# schematics.net
KiCad netlist of a schematic drawn in EAGLE
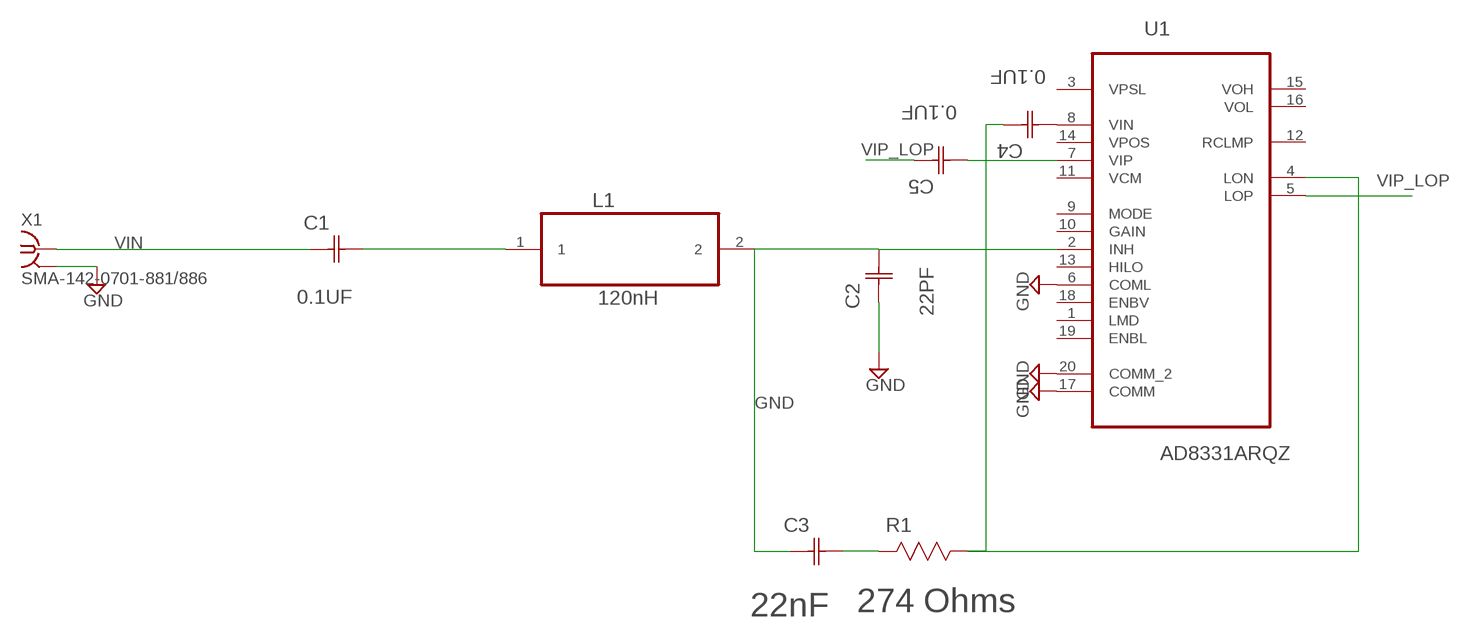
[diagram p0: schematic, sheet 1]

(export (version "E")
  (design (tool "Eeschema 10.0.6"))
  (components
    (comp (ref "C1")
      (value "0.1UF")
      (footprint "eagle-import:CAPC3216X94N")
      (fields (field (name "MPN") "12065C104JAT2A") (field (name "TOLERANCE") "± 5%"))
      (libsource (lib "eagle-import") (part "12065C104JAT2A"))
    )
    (comp (ref "C2")
      (value "22PF")
      (footprint "eagle-import:CAPC3216X94N")
      (fields (field (name "MPN") "12063A220JAT2A") (field (name "TOLERANCE") "±5%"))
      (libsource (lib "eagle-import") (part "12063A220JAT2A"))
    )
    (comp (ref "C3")
      (value "22nF")
      (footprint "eagle-import:CAPC2013X88N")
      (fields (field (name "MPN") "C0805F223K5RACAUTO") (field (name "TOLERANCE") "±10%"))
      (libsource (lib "eagle-import") (part "C0805F223K5RACAUTO"))
    )
    (comp (ref "C4")
      (value "0.1UF")
      (footprint "eagle-import:CAPC3216X94N")
      (fields (field (name "MPN") "12065C104JAT2A") (field (name "TOLERANCE") "± 5%"))
      (libsource (lib "eagle-import") (part "12065C104JAT2A"))
    )
    (comp (ref "C5")
      (value "0.1UF")
      (footprint "eagle-import:CAPC3216X94N")
      (fields (field (name "MPN") "12065C104JAT2A") (field (name "TOLERANCE") "± 5%"))
      (libsource (lib "eagle-import") (part "12065C104JAT2A"))
    )
    (comp (ref "L1")
      (value "120nH")
      (footprint "eagle-import:INDC2317X140N")
      (fields (field (name "MPN") "B82498F3121J") (field (name "TOLERANCE") "±5%"))
      (libsource (lib "eagle-import") (part "B82498F3121J"))
    )
    (comp (ref "R1")
      (value "274 Ohms")
      (footprint "eagle-import:RESC3216X71N")
      (fields (field (name "MPN") "CRCW1206274RFKEA") (field (name "TOLERANCE") "±1%"))
      (libsource (lib "eagle-import") (part "CRCW1206274RFKEA"))
    )
    (comp (ref "U1")
      (value "AD8331ARQZ")
      (footprint "eagle-import:SOP64P600X165-20N")
      (libsource (lib "eagle-import") (part "AD8331ARQZ"))
    )
    (comp (ref "X1")
      (value "SMA-142-0701-881/886")
      (footprint "eagle-import:J502-ND-142-0701-881_886")
      (fields (field (name "MF") "JOHNSON COMPONENTS") (field (name "MPN") "142-0701-881"))
      (libsource (lib "eagle-import") (part "SMA-142-0701-881/886"))
    )
  )
  (nets
    (net (code "1") (name "/VIN") (class "Default")
      (node (ref "C1") (pin "1") (pinfunction "C1_1") (pintype "passive"))
      (node (ref "X1") (pin "1") (pinfunction "1_1") (pintype "passive"))
    )
    (net (code "2") (name "/VIP_LOP") (class "Default")
      (node (ref "C5") (pin "1") (pinfunction "C1_1") (pintype "passive"))
      (node (ref "U1") (pin "5") (pinfunction "LOP_5") (pintype "output"))
    )
    (net (code "3") (name "/VPOS") (class "Default")
      (node (ref "U1") (pin "14") (pinfunction "VPOS_14") (pintype "power_in"))
    )
    (net (code "4") (name "/VPSL") (class "Default")
      (node (ref "U1") (pin "3") (pinfunction "VPSL_3") (pintype "power_in"))
    )
    (net (code "5") (name "GND") (class "Default")
      (node (ref "C2") (pin "1") (pinfunction "C1_1") (pintype "passive"))
      (node (ref "U1") (pin "17") (pinfunction "COMM_17") (pintype "passive"))
      (node (ref "U1") (pin "20") (pinfunction "COMM_2_20") (pintype "passive"))
      (node (ref "U1") (pin "6") (pinfunction "COML_6") (pintype "passive"))
      (node (ref "X1") (pin "G@1") (pinfunction "2_G@1") (pintype "passive"))
      (node (ref "X1") (pin "G@2") (pinfunction "2_G@2") (pintype "passive"))
      (node (ref "X1") (pin "G@3") (pinfunction "2_G@3") (pintype "passive"))
      (node (ref "X1") (pin "G@4") (pinfunction "2_G@4") (pintype "passive"))
    )
    (net (code "6") (name "Net-(C1-C2)") (class "Default")
      (node (ref "C1") (pin "2") (pinfunction "C2_2") (pintype "passive"))
      (node (ref "L1") (pin "1") (pinfunction "1_1") (pintype "passive"))
    )
    (net (code "7") (name "Net-(C2-C2)") (class "Default")
      (node (ref "C2") (pin "2") (pinfunction "C2_2") (pintype "passive"))
      (node (ref "C3") (pin "1") (pinfunction "C1_1") (pintype "passive"))
      (node (ref "L1") (pin "2") (pinfunction "2_2") (pintype "passive"))
      (node (ref "U1") (pin "2") (pinfunction "INH_2") (pintype "input"))
    )
    (net (code "8") (name "Net-(C3-C2)") (class "Default")
      (node (ref "C3") (pin "2") (pinfunction "C2_2") (pintype "passive"))
      (node (ref "R1") (pin "2") (pinfunction "2_2") (pintype "passive"))
    )
    (net (code "9") (name "Net-(C4-C1)") (class "Default")
      (node (ref "C4") (pin "1") (pinfunction "C1_1") (pintype "passive"))
      (node (ref "R1") (pin "1") (pinfunction "1_1") (pintype "passive"))
      (node (ref "U1") (pin "4") (pinfunction "LON_4") (pintype "output"))
    )
    (net (code "10") (name "Net-(C4-C2)") (class "Default")
      (node (ref "C4") (pin "2") (pinfunction "C2_2") (pintype "passive"))
      (node (ref "U1") (pin "8") (pinfunction "VIN_8") (pintype "input"))
    )
    (net (code "11") (name "Net-(C5-C2)") (class "Default")
      (node (ref "C5") (pin "2") (pinfunction "C2_2") (pintype "passive"))
      (node (ref "U1") (pin "7") (pinfunction "VIP_7") (pintype "input"))
    )
    (net (code "12") (name "unconnected-(U1-ENBL-Pad19)") (class "Default")
      (node (ref "U1") (pin "19") (pinfunction "ENBL_19") (pintype "input"))
    )
    (net (code "13") (name "unconnected-(U1-ENBV-Pad18)") (class "Default")
      (node (ref "U1") (pin "18") (pinfunction "ENBV_18") (pintype "input"))
    )
    (net (code "14") (name "unconnected-(U1-GAIN-Pad10)") (class "Default")
      (node (ref "U1") (pin "10") (pinfunction "GAIN_10") (pintype "input"))
    )
    (net (code "15") (name "unconnected-(U1-HILO-Pad13)") (class "Default")
      (node (ref "U1") (pin "13") (pinfunction "HILO_13") (pintype "input"))
    )
    (net (code "16") (name "unconnected-(U1-LMD-Pad1)") (class "Default")
      (node (ref "U1") (pin "1") (pinfunction "LMD_1") (pintype "input"))
    )
    (net (code "17") (name "unconnected-(U1-MODE-Pad9)") (class "Default")
      (node (ref "U1") (pin "9") (pinfunction "MODE_9") (pintype "input"))
    )
    (net (code "18") (name "unconnected-(U1-RCLMP-Pad12)") (class "Default")
      (node (ref "U1") (pin "12") (pinfunction "RCLMP_12") (pintype "output"))
    )
    (net (code "19") (name "unconnected-(U1-VCM-Pad11)") (class "Default")
      (node (ref "U1") (pin "11") (pinfunction "VCM_11") (pintype "input"))
    )
    (net (code "20") (name "unconnected-(U1-VOH-Pad15)") (class "Default")
      (node (ref "U1") (pin "15") (pinfunction "VOH_15") (pintype "output"))
    )
    (net (code "21") (name "unconnected-(U1-VOL-Pad16)") (class "Default")
      (node (ref "U1") (pin "16") (pinfunction "VOL_16") (pintype "output"))
    )
  )
)
